# lm386Amp.net
KiCad netlist of a schematic drawn in EAGLE
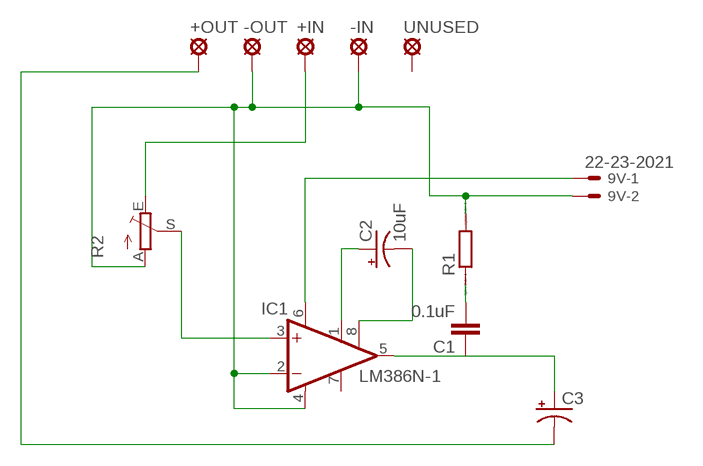
[diagram p0: schematic, sheet 1]

(export (version "E")
  (design (tool "Eeschema 10.0.6"))
  (components
    (comp (ref "+IN")
      (value "LSP10")
      (footprint "eagle-import:LSP10")
      (libsource (lib "eagle-import") (part "LSP10"))
    )
    (comp (ref "+OUT")
      (value "LSP10")
      (footprint "eagle-import:LSP10")
      (libsource (lib "eagle-import") (part "LSP10"))
    )
    (comp (ref "-IN")
      (value "LSP10")
      (footprint "eagle-import:LSP10")
      (libsource (lib "eagle-import") (part "LSP10"))
    )
    (comp (ref "-OUT")
      (value "LSP10")
      (footprint "eagle-import:LSP10")
      (libsource (lib "eagle-import") (part "LSP10"))
    )
    (comp (ref "9V")
      (value "22-23-2021")
      (footprint "eagle-import:22-23-2021")
      (fields (field (name "MF") "MOLEX"))
      (libsource (lib "eagle-import") (part "22-23-2021"))
    )
    (comp (ref "C1")
      (value "0.1uF")
      (footprint "eagle-import:C5B3")
      (libsource (lib "eagle-import") (part "C5/3"))
    )
    (comp (ref "C2")
      (value "10uF")
      (footprint "eagle-import:B45181B")
      (libsource (lib "eagle-import") (part "CPOL-USB45181B"))
    )
    (comp (ref "C3")
      (value "CAP_POLPTH4")
      (footprint "eagle-import:CPOL-RADIAL-1000UF-25V")
      (libsource (lib "eagle-import") (part "CAP_POLPTH4"))
    )
    (comp (ref "IC1")
      (value "LM386N-1")
      (footprint "eagle-import:DIL08")
      (libsource (lib "eagle-import") (part "LM386?-N1"))
    )
    (comp (ref "R1")
      (value "R0204/7")
      (footprint "eagle-import:0204_7")
      (libsource (lib "eagle-import") (part "R0204/7"))
    )
    (comp (ref "R2")
      (value "TRIM_EU-CA14H")
      (footprint "eagle-import:CA14H")
      (libsource (lib "eagle-import") (part "TRIM_EU-CA14H"))
    )
    (comp (ref "UNUSED")
      (value "LSP10")
      (footprint "eagle-import:LSP10")
      (libsource (lib "eagle-import") (part "LSP10"))
    )
  )
  (nets
    (net (code "1") (name "Net-(+IN-PadMP)") (class "Default")
      (node (ref "+IN") (pin "MP") (pinfunction "MP_MP") (pintype "passive"))
      (node (ref "R2") (pin "E") (pinfunction "E_E") (pintype "passive"))
    )
    (net (code "2") (name "Net-(9VA-S)") (class "Default")
      (node (ref "9V") (pin "1") (pinfunction "S_1") (pintype "passive"))
      (node (ref "IC1") (pin "6") (pinfunction "VS_6") (pintype "power_in"))
    )
    (net (code "3") (name "Net-(9VB-S)") (class "Default")
      (node (ref "-IN") (pin "MP") (pinfunction "MP_MP") (pintype "passive"))
      (node (ref "-OUT") (pin "MP") (pinfunction "MP_MP") (pintype "passive"))
      (node (ref "9V") (pin "2") (pinfunction "S_2") (pintype "passive"))
      (node (ref "IC1") (pin "2") (pinfunction "-IN_2") (pintype "input"))
      (node (ref "IC1") (pin "4") (pinfunction "GND_4") (pintype "power_in"))
      (node (ref "R1") (pin "2") (pinfunction "2_2") (pintype "passive"))
      (node (ref "R2") (pin "A") (pinfunction "A_A") (pintype "passive"))
    )
    (net (code "4") (name "Net-(C1-Pad2)") (class "Default")
      (node (ref "C1") (pin "2") (pinfunction "2_2") (pintype "passive"))
      (node (ref "R1") (pin "1") (pinfunction "1_1") (pintype "passive"))
    )
    (net (code "5") (name "Net-(C2-Pad+)") (class "Default")
      (node (ref "C2") (pin "+") (pinfunction "+_+") (pintype "passive"))
      (node (ref "IC1") (pin "1") (pinfunction "GAIN_1") (pintype "passive"))
    )
    (net (code "6") (name "Net-(C2-Pad-)") (class "Default")
      (node (ref "C2") (pin "-") (pinfunction "-_-") (pintype "passive"))
      (node (ref "IC1") (pin "8") (pinfunction "GAIN_8") (pintype "passive"))
    )
    (net (code "7") (name "Net-(C3-+)") (class "Default")
      (node (ref "C1") (pin "1") (pinfunction "1_1") (pintype "passive"))
      (node (ref "C3") (pin "1") (pinfunction "+_1") (pintype "passive"))
      (node (ref "IC1") (pin "5") (pinfunction "OUT_5") (pintype "output"))
    )
    (net (code "8") (name "Net-(C3--)") (class "Default")
      (node (ref "+OUT") (pin "MP") (pinfunction "MP_MP") (pintype "passive"))
      (node (ref "C3") (pin "2") (pinfunction "-_2") (pintype "passive"))
    )
    (net (code "9") (name "Net-(IC1-+IN)") (class "Default")
      (node (ref "IC1") (pin "3") (pinfunction "+IN_3") (pintype "input"))
      (node (ref "R2") (pin "S") (pinfunction "S_S") (pintype "passive"))
    )
    (net (code "10") (name "unconnected-(IC1-BYPASS-Pad7)") (class "Default")
      (node (ref "IC1") (pin "7") (pinfunction "BYPASS_7") (pintype "passive"))
    )
    (net (code "11") (name "unconnected-(UNUSED-PadMP)") (class "Default")
      (node (ref "UNUSED") (pin "MP") (pinfunction "MP_MP") (pintype "passive"))
    )
  )
)
